# ESP_PZEM_v2_1.net
KiCad netlist of a schematic drawn in EAGLE
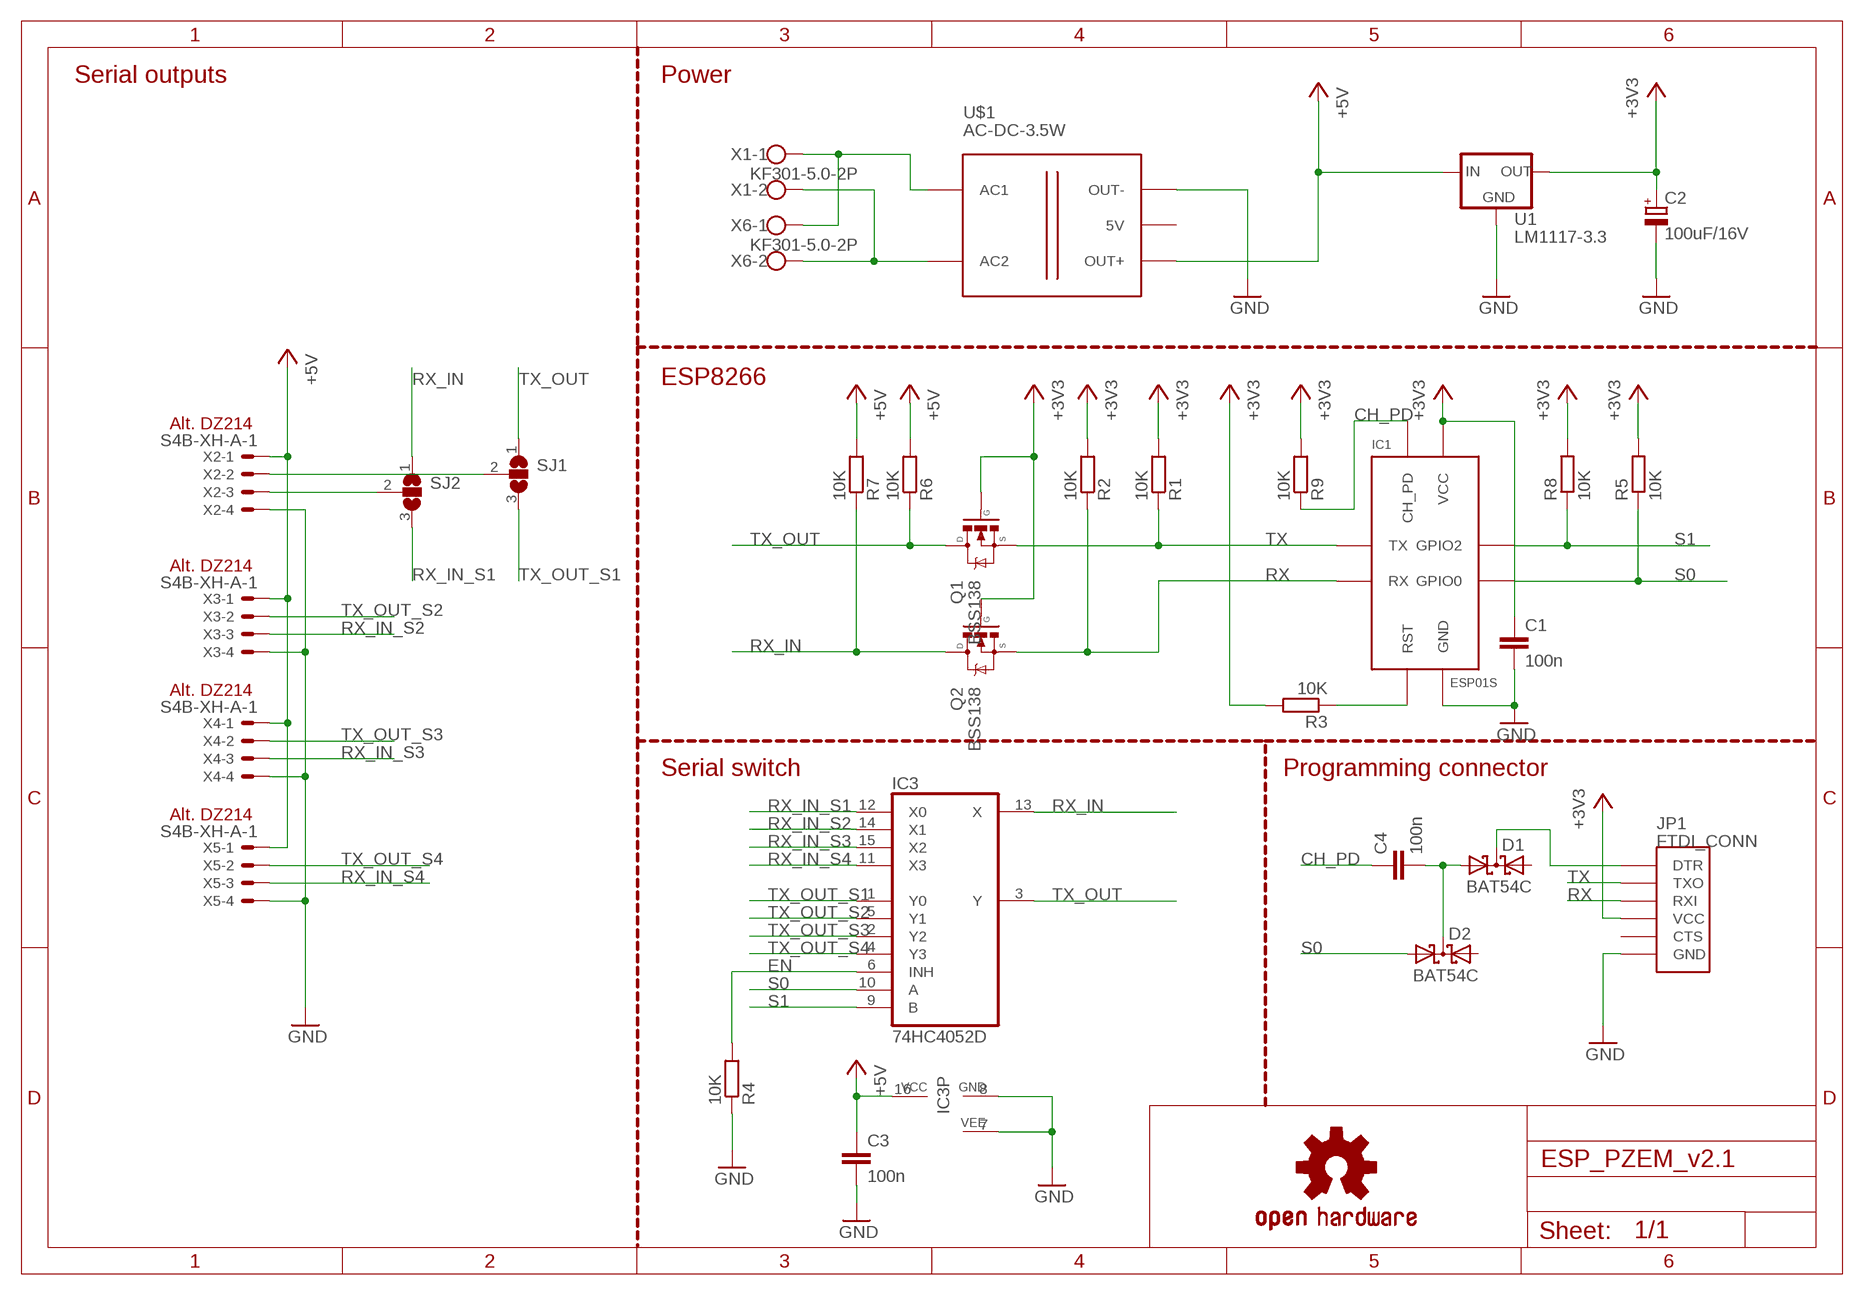
[diagram p0: schematic, sheet 1]

(export (version "E")
  (design (tool "Eeschema 10.0.6"))
  (components
    (comp (ref "C1")
      (value "100n")
      (footprint "eagle-import:C0805")
      (libsource (lib "eagle-import") (part "C-EUC0805"))
    )
    (comp (ref "C2")
      (value "100uF/16V")
      (footprint "eagle-import:SMC_B")
      (libsource (lib "eagle-import") (part "CPOL-EUSMCB"))
    )
    (comp (ref "C3")
      (value "100n")
      (footprint "eagle-import:C0805")
      (libsource (lib "eagle-import") (part "C-EUC0805"))
    )
    (comp (ref "C4")
      (value "100n")
      (footprint "eagle-import:C0805")
      (libsource (lib "eagle-import") (part "C-EUC0805"))
    )
    (comp (ref "D1")
      (value "BAT54C")
      (footprint "eagle-import:SOT23")
      (libsource (lib "eagle-import") (part "BAT54C"))
    )
    (comp (ref "D2")
      (value "BAT54C")
      (footprint "eagle-import:SOT23")
      (libsource (lib "eagle-import") (part "BAT54C"))
    )
    (comp (ref "IC1")
      (value "ESP01S")
      (footprint "eagle-import:ESP-01")
      (libsource (lib "eagle-import") (part "ESP8266-01"))
    )
    (comp (ref "IC3")
      (value "74HC4052D")
      (footprint "eagle-import:SO16")
      (libsource (lib "eagle-import") (part "4052D"))
    )
    (comp (ref "JP1")
      (value "FTDI_CONN")
      (footprint "eagle-import:FTDI")
      (libsource (lib "eagle-import") (part "FTDI_CONN"))
    )
    (comp (ref "LOGO1")
      (value "OSHW-LOGOL")
      (footprint "eagle-import:OSHW-LOGO-L")
      (libsource (lib "eagle-import") (part "OSHW-LOGOL"))
    )
    (comp (ref "Q1")
      (value "BSS138")
      (footprint "eagle-import:SOT23")
      (libsource (lib "eagle-import") (part "BSS138"))
    )
    (comp (ref "Q2")
      (value "BSS138")
      (footprint "eagle-import:SOT23")
      (libsource (lib "eagle-import") (part "BSS138"))
    )
    (comp (ref "R1")
      (value "10K")
      (footprint "eagle-import:R0805")
      (libsource (lib "eagle-import") (part "R-EU_R0805"))
    )
    (comp (ref "R2")
      (value "10K")
      (footprint "eagle-import:R0805")
      (libsource (lib "eagle-import") (part "R-EU_R0805"))
    )
    (comp (ref "R3")
      (value "10K")
      (footprint "eagle-import:R0805")
      (libsource (lib "eagle-import") (part "R-EU_R0805"))
    )
    (comp (ref "R4")
      (value "10K")
      (footprint "eagle-import:R0805")
      (libsource (lib "eagle-import") (part "R-EU_R0805"))
    )
    (comp (ref "R5")
      (value "10K")
      (footprint "eagle-import:R0805")
      (libsource (lib "eagle-import") (part "R-EU_R0805"))
    )
    (comp (ref "R6")
      (value "10K")
      (footprint "eagle-import:R0805")
      (libsource (lib "eagle-import") (part "R-EU_R0805"))
    )
    (comp (ref "R7")
      (value "10K")
      (footprint "eagle-import:R0805")
      (libsource (lib "eagle-import") (part "R-EU_R0805"))
    )
    (comp (ref "R8")
      (value "10K")
      (footprint "eagle-import:R0805")
      (libsource (lib "eagle-import") (part "R-EU_R0805"))
    )
    (comp (ref "R9")
      (value "10K")
      (footprint "eagle-import:R0805")
      (libsource (lib "eagle-import") (part "R-EU_R0805"))
    )
    (comp (ref "SJ1")
      (value "SJ2W")
      (footprint "eagle-import:SJ_2")
      (libsource (lib "eagle-import") (part "SJ2W"))
    )
    (comp (ref "SJ2")
      (value "SJ2W")
      (footprint "eagle-import:SJ_2")
      (libsource (lib "eagle-import") (part "SJ2W"))
    )
    (comp (ref "U$1")
      (value "AC-DC-3.5W")
      (footprint "eagle-import:AC-DC-3.5W")
      (libsource (lib "eagle-import") (part "AC-DC-3.5W"))
    )
    (comp (ref "U1")
      (value "LM1117-3.3")
      (footprint "eagle-import:SOT223")
      (libsource (lib "eagle-import") (part "LM1117-3.3"))
    )
    (comp (ref "X1")
      (value "KF301-5.0-2P")
      (footprint "eagle-import:KF301-5.0-2P")
      (libsource (lib "eagle-import") (part "KF301-5.0-2P"))
    )
    (comp (ref "X2")
      (value "S4B-XH-A-1")
      (footprint "eagle-import:JST-XH-04-PACKAGE-RIGHT")
      (libsource (lib "eagle-import") (part "JST-XH-04-PIN-RIGHT-ANGLE"))
    )
    (comp (ref "X3")
      (value "S4B-XH-A-1")
      (footprint "eagle-import:JST-XH-04-PACKAGE-RIGHT")
      (libsource (lib "eagle-import") (part "JST-XH-04-PIN-RIGHT-ANGLE"))
    )
    (comp (ref "X4")
      (value "S4B-XH-A-1")
      (footprint "eagle-import:JST-XH-04-PACKAGE-RIGHT")
      (libsource (lib "eagle-import") (part "JST-XH-04-PIN-RIGHT-ANGLE"))
    )
    (comp (ref "X5")
      (value "S4B-XH-A-1")
      (footprint "eagle-import:JST-XH-04-PACKAGE-RIGHT")
      (libsource (lib "eagle-import") (part "JST-XH-04-PIN-RIGHT-ANGLE"))
    )
    (comp (ref "X6")
      (value "KF301-5.0-2P")
      (footprint "eagle-import:KF301-5.0-2P")
      (libsource (lib "eagle-import") (part "KF301-5.0-2P"))
    )
  )
  (nets
    (net (code "1") (name "+3V3") (class "Default")
      (node (ref "C1") (pin "1") (pinfunction "1_1") (pintype "passive"))
      (node (ref "C2") (pin "+") (pinfunction "+_+") (pintype "passive"))
      (node (ref "IC1") (pin "VCC") (pinfunction "VCC_VCC") (pintype "power_in"))
      (node (ref "JP1") (pin "P$4") (pinfunction "VCC_P$4") (pintype "bidirectional"))
      (node (ref "Q1") (pin "1") (pinfunction "G_1") (pintype "passive"))
      (node (ref "Q2") (pin "1") (pinfunction "G_1") (pintype "passive"))
      (node (ref "R1") (pin "2") (pinfunction "2_2") (pintype "passive"))
      (node (ref "R2") (pin "2") (pinfunction "2_2") (pintype "passive"))
      (node (ref "R3") (pin "2") (pinfunction "2_2") (pintype "passive"))
      (node (ref "R5") (pin "2") (pinfunction "2_2") (pintype "passive"))
      (node (ref "R8") (pin "2") (pinfunction "2_2") (pintype "passive"))
      (node (ref "R9") (pin "2") (pinfunction "2_2") (pintype "passive"))
      (node (ref "U1") (pin "2") (pinfunction "OUT_2") (pintype "output"))
      (node (ref "U1") (pin "4") (pinfunction "OUT_4") (pintype "output"))
    )
    (net (code "2") (name "+5V") (class "Default")
      (node (ref "C3") (pin "1") (pinfunction "1_1") (pintype "passive"))
      (node (ref "IC3") (pin "16") (pinfunction "VCC_16") (pintype "power_in"))
      (node (ref "R6") (pin "2") (pinfunction "2_2") (pintype "passive"))
      (node (ref "R7") (pin "2") (pinfunction "2_2") (pintype "passive"))
      (node (ref "U$1") (pin "J2.3") (pinfunction "OUT+_J2.3") (pintype "bidirectional"))
      (node (ref "U1") (pin "3") (pinfunction "IN_3") (pintype "input"))
      (node (ref "X2") (pin "1") (pinfunction "S_1") (pintype "passive"))
      (node (ref "X3") (pin "1") (pinfunction "S_1") (pintype "passive"))
      (node (ref "X4") (pin "1") (pinfunction "S_1") (pintype "passive"))
      (node (ref "X5") (pin "1") (pinfunction "S_1") (pintype "passive"))
    )
    (net (code "3") (name "/CH_PD") (class "Default")
      (node (ref "C4") (pin "1") (pinfunction "1_1") (pintype "passive"))
      (node (ref "IC1") (pin "CH_PD") (pinfunction "CH_PD_CH_PD") (pintype "bidirectional"))
      (node (ref "R9") (pin "1") (pinfunction "1_1") (pintype "passive"))
    )
    (net (code "4") (name "/EN") (class "Default")
      (node (ref "IC3") (pin "6") (pinfunction "INH_6") (pintype "input"))
      (node (ref "R4") (pin "2") (pinfunction "2_2") (pintype "passive"))
    )
    (net (code "5") (name "/RX") (class "Default")
      (node (ref "IC1") (pin "RX") (pinfunction "RX_RX") (pintype "input"))
      (node (ref "JP1") (pin "P$3") (pinfunction "RXI_P$3") (pintype "bidirectional"))
      (node (ref "Q2") (pin "2") (pinfunction "S_2") (pintype "passive"))
      (node (ref "R2") (pin "1") (pinfunction "1_1") (pintype "passive"))
    )
    (net (code "6") (name "/RX_IN") (class "Default")
      (node (ref "IC3") (pin "13") (pinfunction "X_13") (pintype "bidirectional"))
      (node (ref "Q2") (pin "3") (pinfunction "D_3") (pintype "passive"))
      (node (ref "R7") (pin "1") (pinfunction "1_1") (pintype "passive"))
      (node (ref "SJ2") (pin "1") (pinfunction "1_1") (pintype "passive"))
    )
    (net (code "7") (name "/RX_IN_S1") (class "Default")
      (node (ref "IC3") (pin "12") (pinfunction "X0_12") (pintype "bidirectional"))
      (node (ref "SJ2") (pin "3") (pinfunction "3_3") (pintype "passive"))
    )
    (net (code "8") (name "/RX_IN_S2") (class "Default")
      (node (ref "IC3") (pin "14") (pinfunction "X1_14") (pintype "bidirectional"))
      (node (ref "X3") (pin "3") (pinfunction "S_3") (pintype "passive"))
    )
    (net (code "9") (name "/RX_IN_S3") (class "Default")
      (node (ref "IC3") (pin "15") (pinfunction "X2_15") (pintype "bidirectional"))
      (node (ref "X4") (pin "3") (pinfunction "S_3") (pintype "passive"))
    )
    (net (code "10") (name "/RX_IN_S4") (class "Default")
      (node (ref "IC3") (pin "11") (pinfunction "X3_11") (pintype "bidirectional"))
      (node (ref "X5") (pin "3") (pinfunction "S_3") (pintype "passive"))
    )
    (net (code "11") (name "/S0") (class "Default")
      (node (ref "D2") (pin "1") (pinfunction "A1_1") (pintype "passive"))
      (node (ref "IC1") (pin "GPIO0") (pinfunction "GPIO0_GPIO0") (pintype "bidirectional"))
      (node (ref "IC3") (pin "10") (pinfunction "A_10") (pintype "input"))
      (node (ref "R5") (pin "1") (pinfunction "1_1") (pintype "passive"))
    )
    (net (code "12") (name "/S1") (class "Default")
      (node (ref "IC1") (pin "GPIO2") (pinfunction "GPIO2_GPIO2") (pintype "bidirectional"))
      (node (ref "IC3") (pin "9") (pinfunction "B_9") (pintype "input"))
      (node (ref "R8") (pin "1") (pinfunction "1_1") (pintype "passive"))
    )
    (net (code "13") (name "/TX") (class "Default")
      (node (ref "IC1") (pin "TX") (pinfunction "TX_TX") (pintype "output"))
      (node (ref "JP1") (pin "P$2") (pinfunction "TXO_P$2") (pintype "bidirectional"))
      (node (ref "Q1") (pin "2") (pinfunction "S_2") (pintype "passive"))
      (node (ref "R1") (pin "1") (pinfunction "1_1") (pintype "passive"))
    )
    (net (code "14") (name "/TX_OUT") (class "Default")
      (node (ref "IC3") (pin "3") (pinfunction "Y_3") (pintype "bidirectional"))
      (node (ref "Q1") (pin "3") (pinfunction "D_3") (pintype "passive"))
      (node (ref "R6") (pin "1") (pinfunction "1_1") (pintype "passive"))
      (node (ref "SJ1") (pin "1") (pinfunction "1_1") (pintype "passive"))
    )
    (net (code "15") (name "/TX_OUT_S1") (class "Default")
      (node (ref "IC3") (pin "1") (pinfunction "Y0_1") (pintype "bidirectional"))
      (node (ref "SJ1") (pin "3") (pinfunction "3_3") (pintype "passive"))
    )
    (net (code "16") (name "/TX_OUT_S2") (class "Default")
      (node (ref "IC3") (pin "5") (pinfunction "Y1_5") (pintype "bidirectional"))
      (node (ref "X3") (pin "2") (pinfunction "S_2") (pintype "passive"))
    )
    (net (code "17") (name "/TX_OUT_S3") (class "Default")
      (node (ref "IC3") (pin "2") (pinfunction "Y2_2") (pintype "bidirectional"))
      (node (ref "X4") (pin "2") (pinfunction "S_2") (pintype "passive"))
    )
    (net (code "18") (name "/TX_OUT_S4") (class "Default")
      (node (ref "IC3") (pin "4") (pinfunction "Y3_4") (pintype "bidirectional"))
      (node (ref "X5") (pin "2") (pinfunction "S_2") (pintype "passive"))
    )
    (net (code "19") (name "GND") (class "Default")
      (node (ref "C1") (pin "2") (pinfunction "2_2") (pintype "passive"))
      (node (ref "C2") (pin "-") (pinfunction "-_-") (pintype "passive"))
      (node (ref "C3") (pin "2") (pinfunction "2_2") (pintype "passive"))
      (node (ref "IC1") (pin "GND") (pinfunction "GND_GND") (pintype "power_in"))
      (node (ref "IC3") (pin "7") (pinfunction "VEE_7") (pintype "power_in"))
      (node (ref "IC3") (pin "8") (pinfunction "GND_8") (pintype "power_in"))
      (node (ref "JP1") (pin "P$6") (pinfunction "GND_P$6") (pintype "bidirectional"))
      (node (ref "R4") (pin "1") (pinfunction "1_1") (pintype "passive"))
      (node (ref "U$1") (pin "J2.1") (pinfunction "OUT-_J2.1") (pintype "bidirectional"))
      (node (ref "U1") (pin "1") (pinfunction "GND_1") (pintype "input"))
      (node (ref "X2") (pin "4") (pinfunction "S_4") (pintype "passive"))
      (node (ref "X3") (pin "4") (pinfunction "S_4") (pintype "passive"))
      (node (ref "X4") (pin "4") (pinfunction "S_4") (pintype "passive"))
      (node (ref "X5") (pin "4") (pinfunction "S_4") (pintype "passive"))
    )
    (net (code "20") (name "Net-(D1-A1)") (class "Default")
      (node (ref "C4") (pin "2") (pinfunction "2_2") (pintype "passive"))
      (node (ref "D1") (pin "1") (pinfunction "A1_1") (pintype "passive"))
      (node (ref "D2") (pin "3") (pinfunction "CC_3") (pintype "passive"))
    )
    (net (code "21") (name "Net-(D1-CC)") (class "Default")
      (node (ref "D1") (pin "3") (pinfunction "CC_3") (pintype "passive"))
      (node (ref "JP1") (pin "P$1") (pinfunction "DTR_P$1") (pintype "bidirectional"))
    )
    (net (code "22") (name "Net-(IC1-PadRST)") (class "Default")
      (node (ref "IC1") (pin "RST") (pinfunction "RST_RST") (pintype "bidirectional"))
      (node (ref "R3") (pin "1") (pinfunction "1_1") (pintype "passive"))
    )
    (net (code "23") (name "Net-(U$1-AC1)") (class "Default")
      (node (ref "U$1") (pin "J1.1") (pinfunction "AC1_J1.1") (pintype "bidirectional"))
      (node (ref "X1") (pin "1") (pinfunction "KL_1") (pintype "passive"))
      (node (ref "X6") (pin "1") (pinfunction "KL_1") (pintype "passive"))
    )
    (net (code "24") (name "Net-(U$1-AC2)") (class "Default")
      (node (ref "U$1") (pin "J1.2") (pinfunction "AC2_J1.2") (pintype "bidirectional"))
      (node (ref "X1") (pin "2") (pinfunction "KL_2") (pintype "passive"))
      (node (ref "X6") (pin "2") (pinfunction "KL_2") (pintype "passive"))
    )
    (net (code "25") (name "Net-(X2B-S)") (class "Default")
      (node (ref "SJ1") (pin "2") (pinfunction "2_2") (pintype "passive"))
      (node (ref "X2") (pin "2") (pinfunction "S_2") (pintype "passive"))
    )
    (net (code "26") (name "Net-(X2C-S)") (class "Default")
      (node (ref "SJ2") (pin "2") (pinfunction "2_2") (pintype "passive"))
      (node (ref "X2") (pin "3") (pinfunction "S_3") (pintype "passive"))
    )
    (net (code "27") (name "unconnected-(D1-A2-Pad2)") (class "Default")
      (node (ref "D1") (pin "2") (pinfunction "A2_2") (pintype "passive"))
    )
    (net (code "28") (name "unconnected-(D2-A2-Pad2)") (class "Default")
      (node (ref "D2") (pin "2") (pinfunction "A2_2") (pintype "passive"))
    )
    (net (code "29") (name "unconnected-(JP1-CTS-PadP$5)") (class "Default")
      (node (ref "JP1") (pin "P$5") (pinfunction "CTS_P$5") (pintype "bidirectional"))
    )
    (net (code "30") (name "unconnected-(U$1-5V-PadJ2.2)") (class "Default")
      (node (ref "U$1") (pin "J2.2") (pinfunction "5V_J2.2") (pintype "bidirectional"))
    )
  )
)
